# LeafSch.net
KiCad netlist of a schematic drawn in Altium Designer
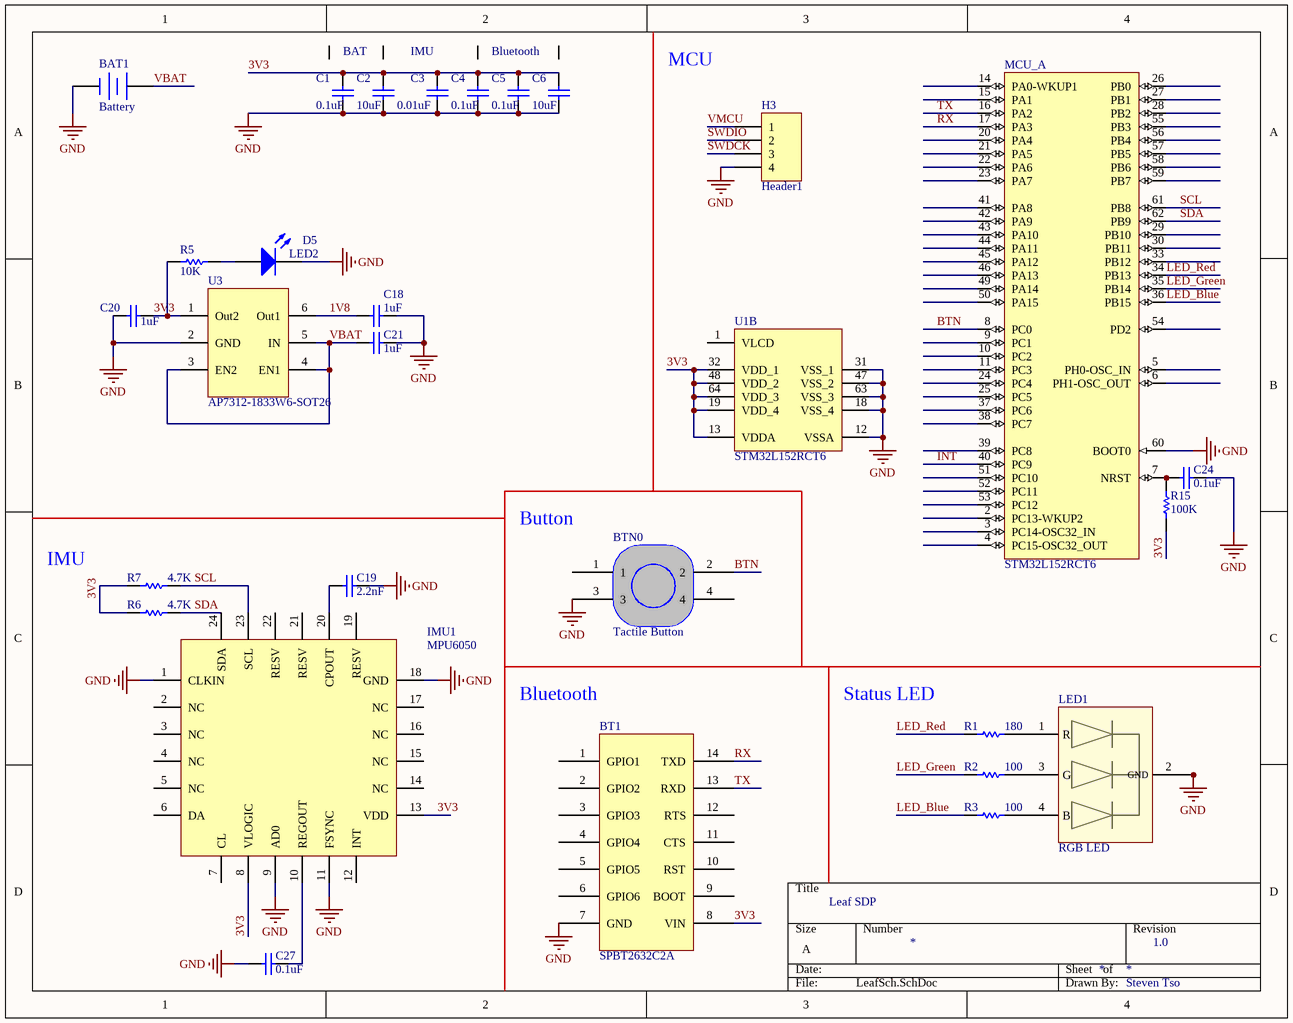
[diagram p0: LeafSch.SchDoc]

(export (version "E")
  (design (tool "Eeschema 10.0.6"))
  (components
    (comp (ref "BAT1")
      (value "Battery")
      (footprint "BAT-2")
      (description "Multicell Battery")
      (fields (field (name "PUBLISHER") "Altium Limited"))
      (libsource (lib "Miscellaneous Devices") (part "Battery"))
    )
    (comp (ref "BT1")
      (value "SPBT2632C2A")
      (footprint "SPBT2632C2A")
      (libsource (lib "myLib") (part "SPBT2632C2A"))
    )
    (comp (ref "BTN0") (value "Tactile Button") (libsource (lib "myLib") (part "Tactile Button")))
    (comp (ref "C1")
      (value "0.1uF")
      (footprint "CAPC0805(2012)100_N")
      (description "CAP 1uF 16V -20% to +80% 0805 (2012 Metric) Thickness 1mm SMD")
      (fields (field (name "TOLERANCE") "-20% to +80%"))
      (libsource (lib "Altium Content Vault") (part "CMP-1036-04751-1"))
    )
    (comp (ref "C2")
      (value "10uF")
      (footprint "CAPC0805(2012)100_N")
      (description "CAP 1uF 16V -20% to +80% 0805 (2012 Metric) Thickness 1mm SMD")
      (fields (field (name "TOLERANCE") "-20% to +80%"))
      (libsource (lib "Altium Content Vault") (part "CMP-1036-04751-1"))
    )
    (comp (ref "C3")
      (value "0.01uF")
      (footprint "CAPC0805(2012)100_N")
      (description "CAP 1uF 16V -20% to +80% 0805 (2012 Metric) Thickness 1mm SMD")
      (fields (field (name "TOLERANCE") "-20% to +80%"))
      (libsource (lib "Altium Content Vault") (part "CMP-1036-04751-1"))
    )
    (comp (ref "C4")
      (value "0.1uF")
      (footprint "CAPC0805(2012)100_N")
      (description "CAP 1uF 16V -20% to +80% 0805 (2012 Metric) Thickness 1mm SMD")
      (fields (field (name "TOLERANCE") "-20% to +80%"))
      (libsource (lib "Altium Content Vault") (part "CMP-1036-04751-1"))
    )
    (comp (ref "C5")
      (value "0.1uF")
      (footprint "CAPC0805(2012)100_N")
      (description "CAP 1uF 16V -20% to +80% 0805 (2012 Metric) Thickness 1mm SMD")
      (fields (field (name "TOLERANCE") "-20% to +80%"))
      (libsource (lib "Altium Content Vault") (part "CMP-1036-04751-1"))
    )
    (comp (ref "C6")
      (value "10uF")
      (footprint "CAPC0805(2012)100_N")
      (description "CAP 1uF 16V -20% to +80% 0805 (2012 Metric) Thickness 1mm SMD")
      (fields (field (name "TOLERANCE") "-20% to +80%"))
      (libsource (lib "Altium Content Vault") (part "CMP-1036-04751-1"))
    )
    (comp (ref "C18")
      (value "1uF")
      (footprint "CAPC0603(1608)100_M")
      (description "CAP 1uF 16V -20% to +80% 0603 (1608 Metric) Thickness 1mm SMD")
      (fields (field (name "TOLERANCE") "-20% to +80%"))
      (libsource (lib "Altium Content Vault") (part "CMP-1035-02739-1"))
    )
    (comp (ref "C19")
      (value "2.2nF")
      (footprint "CAPC0603(1608)100_M")
      (description "CAP 1uF 16V -20% to +80% 0603 (1608 Metric) Thickness 1mm SMD")
      (fields (field (name "TOLERANCE") "-20% to +80%"))
      (libsource (lib "Altium Content Vault") (part "CMP-1035-02739-1"))
    )
    (comp (ref "C20")
      (value "1uF")
      (footprint "CAPC0603(1608)100_M")
      (description "CAP 1uF 16V -20% to +80% 0603 (1608 Metric) Thickness 1mm SMD")
      (fields (field (name "TOLERANCE") "-20% to +80%"))
      (libsource (lib "Altium Content Vault") (part "CMP-1035-02739-1"))
    )
    (comp (ref "C21")
      (value "1uF")
      (footprint "CAPC0603(1608)100_M")
      (description "CAP 1uF 16V -20% to +80% 0603 (1608 Metric) Thickness 1mm SMD")
      (fields (field (name "TOLERANCE") "-20% to +80%"))
      (libsource (lib "Altium Content Vault") (part "CMP-1035-02739-1"))
    )
    (comp (ref "C24")
      (value "0.1uF")
      (footprint "CAPC0603(1608)100_M")
      (description "CAP 1uF 16V -20% to +80% 0603 (1608 Metric) Thickness 1mm SMD")
      (fields (field (name "TOLERANCE") "-20% to +80%"))
      (libsource (lib "Altium Content Vault") (part "CMP-1035-02739-1"))
    )
    (comp (ref "C27")
      (value "0.1uF")
      (footprint "CAPC0603(1608)100_M")
      (description "CAP 1uF 16V -20% to +80% 0603 (1608 Metric) Thickness 1mm SMD")
      (fields (field (name "TOLERANCE") "-20% to +80%"))
      (libsource (lib "Altium Content Vault") (part "CMP-1035-02739-1"))
    )
    (comp (ref "D5")
      (value "LED2")
      (footprint "3.2X1.6X1.1")
      (description "Typical RED, GREEN, YELLOW, AMBER GaAs LED")
      (fields (field (name "PUBLISHER") "Altium Limited"))
      (libsource (lib "Miscellaneous Devices") (part "LED2"))
    )
    (comp (ref "H3")
      (value "Header1")
      (footprint "HDR1X4")
      (description "Header, 4-Pin")
      (fields (field (name "PUBLISHER") "Altium Limited"))
      (libsource (lib "Miscellaneous Connectors") (part "Header 4"))
    )
    (comp (ref "IMU1") (value "MPU6050") (libsource (lib "myLib") (part "MPU6050")))
    (comp (ref "LED1") (value "RGB LED") (libsource (lib "myLib") (part "RGB LED")))
    (comp (ref "MCU_")
      (value "STM32L152RCT6")
      (footprint "STM-LQFP64_N")
      (libsource (lib "STMicroelectronics STM32 L1") (part "STM32L152RCT6"))
    )
    (comp (ref "R1")
      (value "180")
      (footprint "RESC0603(1608)_L")
      (description "10K 0.1W 5% 0603 (1608 Metric)  SMD")
      (fields (field (name "TOLERANCE") "5 %") (field (name "POWER") "0.1 W"))
      (libsource (lib "Altium Content Vault") (part "CMP-1012-00074-1"))
    )
    (comp (ref "R2")
      (value "100")
      (footprint "RESC0603(1608)_L")
      (description "10K 0.1W 5% 0603 (1608 Metric)  SMD")
      (fields (field (name "TOLERANCE") "5 %") (field (name "POWER") "0.1 W"))
      (libsource (lib "Altium Content Vault") (part "CMP-1012-00074-1"))
    )
    (comp (ref "R3")
      (value "100")
      (footprint "RESC0603(1608)_L")
      (description "10K 0.1W 5% 0603 (1608 Metric)  SMD")
      (fields (field (name "TOLERANCE") "5 %") (field (name "POWER") "0.1 W"))
      (libsource (lib "Altium Content Vault") (part "CMP-1012-00074-1"))
    )
    (comp (ref "R5")
      (value "10K")
      (footprint "RESC0603(1608)_L")
      (description "10K 0.1W 5% 0603 (1608 Metric)  SMD")
      (fields (field (name "TOLERANCE") "5 %") (field (name "POWER") "0.1 W"))
      (libsource (lib "Altium Content Vault") (part "CMP-1012-00074-1"))
    )
    (comp (ref "R6")
      (value "4.7K")
      (footprint "RESC0603(1608)_L")
      (description "10K 0.1W 5% 0603 (1608 Metric)  SMD")
      (fields (field (name "TOLERANCE") "5 %") (field (name "POWER") "0.1 W"))
      (libsource (lib "Altium Content Vault") (part "CMP-1012-00074-1"))
    )
    (comp (ref "R7")
      (value "4.7K")
      (footprint "RESC0603(1608)_L")
      (description "10K 0.1W 5% 0603 (1608 Metric)  SMD")
      (fields (field (name "TOLERANCE") "5 %") (field (name "POWER") "0.1 W"))
      (libsource (lib "Altium Content Vault") (part "CMP-1012-00074-1"))
    )
    (comp (ref "R15")
      (value "100K")
      (footprint "RESC0603(1608)_L")
      (description "10K 0.1W 5% 0603 (1608 Metric)  SMD")
      (fields (field (name "TOLERANCE") "5 %") (field (name "POWER") "0.1 W"))
      (libsource (lib "Altium Content Vault") (part "CMP-1012-00074-1"))
    )
    (comp (ref "U1")
      (value "STM32L152RCT6")
      (footprint "STM-LQFP64_N")
      (libsource (lib "STMicroelectronics STM32 L1") (part "STM32L152RCT6"))
    )
    (comp (ref "U3")
      (value "AP7312-1833W6-SOT26")
      (footprint "SOT26A-6AN")
      (libsource (lib "myLib") (part "AP7312-1833W6-SOT26"))
    )
  )
  (nets
    (net (code "1") (name "/1V8") (class "Default")
      (node (ref "C18") (pin "2") (pinfunction "2_2") (pintype "passive"))
      (node (ref "U3") (pin "6") (pinfunction "Out1_6") (pintype "passive"))
    )
    (net (code "2") (name "/3V3") (class "Default")
      (node (ref "BT1") (pin "8") (pinfunction "VIN_8") (pintype "passive"))
      (node (ref "C1") (pin "1") (pinfunction "1_1") (pintype "passive"))
      (node (ref "C2") (pin "1") (pinfunction "1_1") (pintype "passive"))
      (node (ref "C20") (pin "1") (pinfunction "1_1") (pintype "passive"))
      (node (ref "C3") (pin "1") (pinfunction "1_1") (pintype "passive"))
      (node (ref "C4") (pin "1") (pinfunction "1_1") (pintype "passive"))
      (node (ref "C5") (pin "1") (pinfunction "1_1") (pintype "passive"))
      (node (ref "C6") (pin "1") (pinfunction "1_1") (pintype "passive"))
      (node (ref "IMU1") (pin "13") (pinfunction "VDD_13") (pintype "passive"))
      (node (ref "IMU1") (pin "8") (pinfunction "VLOGIC_8") (pintype "passive"))
      (node (ref "R15") (pin "1") (pinfunction "1_1") (pintype "passive"))
      (node (ref "R5") (pin "2") (pinfunction "2_2") (pintype "passive"))
      (node (ref "R6") (pin "1") (pinfunction "1_1") (pintype "passive"))
      (node (ref "R7") (pin "1") (pinfunction "1_1") (pintype "passive"))
      (node (ref "U1") (pin "13") (pinfunction "VDDA_13") (pintype "power_in"))
      (node (ref "U1") (pin "19") (pinfunction "VDD_4_19") (pintype "power_in"))
      (node (ref "U1") (pin "32") (pinfunction "VDD_1_32") (pintype "power_in"))
      (node (ref "U1") (pin "48") (pinfunction "VDD_2_48") (pintype "power_in"))
      (node (ref "U1") (pin "64") (pinfunction "VDD_3_64") (pintype "power_in"))
      (node (ref "U3") (pin "1") (pinfunction "Out2_1") (pintype "passive"))
    )
    (net (code "3") (name "/BTN") (class "Default")
      (node (ref "BTN0") (pin "2") (pinfunction "2_2") (pintype "passive"))
      (node (ref "MCU_") (pin "8") (pinfunction "PC0_8") (pintype "bidirectional"))
    )
    (net (code "4") (name "/INT") (class "Default")
      (node (ref "MCU_") (pin "40") (pinfunction "PC9_40") (pintype "bidirectional"))
    )
    (net (code "5") (name "/LED_Blue") (class "Default")
      (node (ref "MCU_") (pin "36") (pinfunction "PB15_36") (pintype "bidirectional"))
      (node (ref "R3") (pin "2") (pinfunction "2_2") (pintype "passive"))
    )
    (net (code "6") (name "/LED_Green") (class "Default")
      (node (ref "MCU_") (pin "35") (pinfunction "PB14_35") (pintype "bidirectional"))
      (node (ref "R2") (pin "2") (pinfunction "2_2") (pintype "passive"))
    )
    (net (code "7") (name "/LED_Red") (class "Default")
      (node (ref "MCU_") (pin "34") (pinfunction "PB13_34") (pintype "bidirectional"))
      (node (ref "R1") (pin "2") (pinfunction "2_2") (pintype "passive"))
    )
    (net (code "8") (name "/RX") (class "Default")
      (node (ref "BT1") (pin "14") (pinfunction "TXD_14") (pintype "passive"))
      (node (ref "MCU_") (pin "17") (pinfunction "PA3_17") (pintype "bidirectional"))
    )
    (net (code "9") (name "/SCL") (class "Default")
      (node (ref "IMU1") (pin "23") (pinfunction "SCL_23") (pintype "passive"))
      (node (ref "MCU_") (pin "61") (pinfunction "PB8_61") (pintype "bidirectional"))
      (node (ref "R7") (pin "2") (pinfunction "2_2") (pintype "passive"))
    )
    (net (code "10") (name "/SDA") (class "Default")
      (node (ref "IMU1") (pin "24") (pinfunction "SDA_24") (pintype "passive"))
      (node (ref "MCU_") (pin "62") (pinfunction "PB9_62") (pintype "bidirectional"))
      (node (ref "R6") (pin "2") (pinfunction "2_2") (pintype "passive"))
    )
    (net (code "11") (name "/SWDCK") (class "Default")
      (node (ref "H3") (pin "3") (pinfunction "3_3") (pintype "passive"))
    )
    (net (code "12") (name "/SWDIO") (class "Default")
      (node (ref "H3") (pin "2") (pinfunction "2_2") (pintype "passive"))
    )
    (net (code "13") (name "/TX") (class "Default")
      (node (ref "BT1") (pin "13") (pinfunction "RXD_13") (pintype "passive"))
      (node (ref "MCU_") (pin "16") (pinfunction "PA2_16") (pintype "bidirectional"))
    )
    (net (code "14") (name "/VBAT") (class "Default")
      (node (ref "BAT1") (pin "1") (pinfunction "+_1") (pintype "passive"))
      (node (ref "C21") (pin "2") (pinfunction "2_2") (pintype "passive"))
      (node (ref "U3") (pin "3") (pinfunction "EN2_3") (pintype "passive"))
      (node (ref "U3") (pin "4") (pinfunction "EN1_4") (pintype "passive"))
      (node (ref "U3") (pin "5") (pinfunction "IN_5") (pintype "passive"))
    )
    (net (code "15") (name "/VMCU") (class "Default")
      (node (ref "H3") (pin "1") (pinfunction "1_1") (pintype "passive"))
    )
    (net (code "16") (name "GND") (class "Default")
      (node (ref "BAT1") (pin "2") (pinfunction "-_2") (pintype "passive"))
      (node (ref "BT1") (pin "7") (pinfunction "GND_7") (pintype "passive"))
      (node (ref "BTN0") (pin "3") (pinfunction "3_3") (pintype "passive"))
      (node (ref "C1") (pin "2") (pinfunction "2_2") (pintype "passive"))
      (node (ref "C18") (pin "1") (pinfunction "1_1") (pintype "passive"))
      (node (ref "C19") (pin "1") (pinfunction "1_1") (pintype "passive"))
      (node (ref "C2") (pin "2") (pinfunction "2_2") (pintype "passive"))
      (node (ref "C20") (pin "2") (pinfunction "2_2") (pintype "passive"))
      (node (ref "C21") (pin "1") (pinfunction "1_1") (pintype "passive"))
      (node (ref "C24") (pin "1") (pinfunction "1_1") (pintype "passive"))
      (node (ref "C27") (pin "2") (pinfunction "2_2") (pintype "passive"))
      (node (ref "C3") (pin "2") (pinfunction "2_2") (pintype "passive"))
      (node (ref "C4") (pin "2") (pinfunction "2_2") (pintype "passive"))
      (node (ref "C5") (pin "2") (pinfunction "2_2") (pintype "passive"))
      (node (ref "C6") (pin "2") (pinfunction "2_2") (pintype "passive"))
      (node (ref "D5") (pin "2") (pinfunction "K_2") (pintype "passive"))
      (node (ref "H3") (pin "4") (pinfunction "4_4") (pintype "passive"))
      (node (ref "IMU1") (pin "1") (pinfunction "CLKIN_1") (pintype "passive"))
      (node (ref "IMU1") (pin "11") (pinfunction "FSYNC_11") (pintype "passive"))
      (node (ref "IMU1") (pin "18") (pinfunction "GND_18") (pintype "passive"))
      (node (ref "IMU1") (pin "9") (pinfunction "AD0_9") (pintype "passive"))
      (node (ref "LED1") (pin "2") (pinfunction "GND_2") (pintype "passive"))
      (node (ref "MCU_") (pin "60") (pinfunction "BOOT0_60") (pintype "input"))
      (node (ref "U1") (pin "12") (pinfunction "VSSA_12") (pintype "power_in"))
      (node (ref "U1") (pin "18") (pinfunction "VSS_4_18") (pintype "power_in"))
      (node (ref "U1") (pin "31") (pinfunction "VSS_1_31") (pintype "power_in"))
      (node (ref "U1") (pin "47") (pinfunction "VSS_2_47") (pintype "power_in"))
      (node (ref "U1") (pin "63") (pinfunction "VSS_3_63") (pintype "power_in"))
      (node (ref "U3") (pin "2") (pinfunction "GND_2") (pintype "passive"))
    )
    (net (code "17") (name "Net-(D5-A)") (class "Default")
      (node (ref "D5") (pin "1") (pinfunction "A_1") (pintype "passive"))
      (node (ref "R5") (pin "1") (pinfunction "1_1") (pintype "passive"))
    )
    (net (code "18") (name "Net-(IMU1-CPOUT)") (class "Default")
      (node (ref "C19") (pin "2") (pinfunction "2_2") (pintype "passive"))
      (node (ref "IMU1") (pin "20") (pinfunction "CPOUT_20") (pintype "passive"))
    )
    (net (code "19") (name "Net-(IMU1-REGOUT)") (class "Default")
      (node (ref "C27") (pin "1") (pinfunction "1_1") (pintype "passive"))
      (node (ref "IMU1") (pin "10") (pinfunction "REGOUT_10") (pintype "passive"))
    )
    (net (code "20") (name "Net-(LED1-B)") (class "Default")
      (node (ref "LED1") (pin "4") (pinfunction "B_4") (pintype "passive"))
      (node (ref "R3") (pin "1") (pinfunction "1_1") (pintype "passive"))
    )
    (net (code "21") (name "Net-(LED1-G)") (class "Default")
      (node (ref "LED1") (pin "3") (pinfunction "G_3") (pintype "passive"))
      (node (ref "R2") (pin "1") (pinfunction "1_1") (pintype "passive"))
    )
    (net (code "22") (name "Net-(LED1-R)") (class "Default")
      (node (ref "LED1") (pin "1") (pinfunction "R_1") (pintype "passive"))
      (node (ref "R1") (pin "1") (pinfunction "1_1") (pintype "passive"))
    )
    (net (code "23") (name "Net-(MCU_A-NRST)") (class "Default")
      (node (ref "C24") (pin "2") (pinfunction "2_2") (pintype "passive"))
      (node (ref "MCU_") (pin "7") (pinfunction "NRST_7") (pintype "bidirectional"))
      (node (ref "R15") (pin "2") (pinfunction "2_2") (pintype "passive"))
    )
    (net (code "24") (name "unconnected-(BT1-BOOT-Pad9)") (class "Default")
      (node (ref "BT1") (pin "9") (pinfunction "BOOT_9") (pintype "passive"))
    )
    (net (code "25") (name "unconnected-(BT1-CTS-Pad11)") (class "Default")
      (node (ref "BT1") (pin "11") (pinfunction "CTS_11") (pintype "passive"))
    )
    (net (code "26") (name "unconnected-(BT1-GPIO1-Pad1)") (class "Default")
      (node (ref "BT1") (pin "1") (pinfunction "GPIO1_1") (pintype "passive"))
    )
    (net (code "27") (name "unconnected-(BT1-GPIO2-Pad2)") (class "Default")
      (node (ref "BT1") (pin "2") (pinfunction "GPIO2_2") (pintype "passive"))
    )
    (net (code "28") (name "unconnected-(BT1-GPIO3-Pad3)") (class "Default")
      (node (ref "BT1") (pin "3") (pinfunction "GPIO3_3") (pintype "passive"))
    )
    (net (code "29") (name "unconnected-(BT1-GPIO4-Pad4)") (class "Default")
      (node (ref "BT1") (pin "4") (pinfunction "GPIO4_4") (pintype "passive"))
    )
    (net (code "30") (name "unconnected-(BT1-GPIO5-Pad5)") (class "Default")
      (node (ref "BT1") (pin "5") (pinfunction "GPIO5_5") (pintype "passive"))
    )
    (net (code "31") (name "unconnected-(BT1-GPIO6-Pad6)") (class "Default")
      (node (ref "BT1") (pin "6") (pinfunction "GPIO6_6") (pintype "passive"))
    )
    (net (code "32") (name "unconnected-(BT1-RST-Pad10)") (class "Default")
      (node (ref "BT1") (pin "10") (pinfunction "RST_10") (pintype "passive"))
    )
    (net (code "33") (name "unconnected-(BT1-RTS-Pad12)") (class "Default")
      (node (ref "BT1") (pin "12") (pinfunction "RTS_12") (pintype "passive"))
    )
    (net (code "34") (name "unconnected-(BTN0-Pad1)") (class "Default")
      (node (ref "BTN0") (pin "1") (pinfunction "1_1") (pintype "passive"))
    )
    (net (code "35") (name "unconnected-(BTN0-Pad4)") (class "Default")
      (node (ref "BTN0") (pin "4") (pinfunction "4_4") (pintype "passive"))
    )
    (net (code "36") (name "unconnected-(IMU1-CL-Pad7)") (class "Default")
      (node (ref "IMU1") (pin "7") (pinfunction "CL_7") (pintype "passive"))
    )
    (net (code "37") (name "unconnected-(IMU1-DA-Pad6)") (class "Default")
      (node (ref "IMU1") (pin "6") (pinfunction "DA_6") (pintype "passive"))
    )
    (net (code "38") (name "unconnected-(IMU1-INT-Pad12)") (class "Default")
      (node (ref "IMU1") (pin "12") (pinfunction "INT_12") (pintype "passive"))
    )
    (net (code "39") (name "unconnected-(IMU1-NC-Pad2)") (class "Default")
      (node (ref "IMU1") (pin "2") (pinfunction "NC_2") (pintype "passive"))
    )
    (net (code "40") (name "unconnected-(IMU1-NC-Pad3)") (class "Default")
      (node (ref "IMU1") (pin "3") (pinfunction "NC_3") (pintype "passive"))
    )
    (net (code "41") (name "unconnected-(IMU1-NC-Pad4)") (class "Default")
      (node (ref "IMU1") (pin "4") (pinfunction "NC_4") (pintype "passive"))
    )
    (net (code "42") (name "unconnected-(IMU1-NC-Pad5)") (class "Default")
      (node (ref "IMU1") (pin "5") (pinfunction "NC_5") (pintype "passive"))
    )
    (net (code "43") (name "unconnected-(IMU1-NC-Pad14)") (class "Default")
      (node (ref "IMU1") (pin "14") (pinfunction "NC_14") (pintype "passive"))
    )
    (net (code "44") (name "unconnected-(IMU1-NC-Pad15)") (class "Default")
      (node (ref "IMU1") (pin "15") (pinfunction "NC_15") (pintype "passive"))
    )
    (net (code "45") (name "unconnected-(IMU1-NC-Pad16)") (class "Default")
      (node (ref "IMU1") (pin "16") (pinfunction "NC_16") (pintype "passive"))
    )
    (net (code "46") (name "unconnected-(IMU1-NC-Pad17)") (class "Default")
      (node (ref "IMU1") (pin "17") (pinfunction "NC_17") (pintype "passive"))
    )
    (net (code "47") (name "unconnected-(IMU1-RESV-Pad19)") (class "Default")
      (node (ref "IMU1") (pin "19") (pinfunction "RESV_19") (pintype "passive"))
    )
    (net (code "48") (name "unconnected-(IMU1-RESV-Pad21)") (class "Default")
      (node (ref "IMU1") (pin "21") (pinfunction "RESV_21") (pintype "passive"))
    )
    (net (code "49") (name "unconnected-(IMU1-RESV-Pad22)") (class "Default")
      (node (ref "IMU1") (pin "22") (pinfunction "RESV_22") (pintype "passive"))
    )
    (net (code "50") (name "unconnected-(MCU_A-PA0-WKUP1-Pad14)") (class "Default")
      (node (ref "MCU_") (pin "14") (pinfunction "PA0-WKUP1_14") (pintype "bidirectional"))
    )
    (net (code "51") (name "unconnected-(MCU_A-PA1-Pad15)") (class "Default")
      (node (ref "MCU_") (pin "15") (pinfunction "PA1_15") (pintype "bidirectional"))
    )
    (net (code "52") (name "unconnected-(MCU_A-PA4-Pad20)") (class "Default")
      (node (ref "MCU_") (pin "20") (pinfunction "PA4_20") (pintype "bidirectional"))
    )
    (net (code "53") (name "unconnected-(MCU_A-PA5-Pad21)") (class "Default")
      (node (ref "MCU_") (pin "21") (pinfunction "PA5_21") (pintype "bidirectional"))
    )
    (net (code "54") (name "unconnected-(MCU_A-PA6-Pad22)") (class "Default")
      (node (ref "MCU_") (pin "22") (pinfunction "PA6_22") (pintype "bidirectional"))
    )
    (net (code "55") (name "unconnected-(MCU_A-PA7-Pad23)") (class "Default")
      (node (ref "MCU_") (pin "23") (pinfunction "PA7_23") (pintype "bidirectional"))
    )
    (net (code "56") (name "unconnected-(MCU_A-PA8-Pad41)") (class "Default")
      (node (ref "MCU_") (pin "41") (pinfunction "PA8_41") (pintype "bidirectional"))
    )
    (net (code "57") (name "unconnected-(MCU_A-PA9-Pad42)") (class "Default")
      (node (ref "MCU_") (pin "42") (pinfunction "PA9_42") (pintype "bidirectional"))
    )
    (net (code "58") (name "unconnected-(MCU_A-PA10-Pad43)") (class "Default")
      (node (ref "MCU_") (pin "43") (pinfunction "PA10_43") (pintype "bidirectional"))
    )
    (net (code "59") (name "unconnected-(MCU_A-PA11-Pad44)") (class "Default")
      (node (ref "MCU_") (pin "44") (pinfunction "PA11_44") (pintype "bidirectional"))
    )
    (net (code "60") (name "unconnected-(MCU_A-PA12-Pad45)") (class "Default")
      (node (ref "MCU_") (pin "45") (pinfunction "PA12_45") (pintype "bidirectional"))
    )
    (net (code "61") (name "unconnected-(MCU_A-PA13-Pad46)") (class "Default")
      (node (ref "MCU_") (pin "46") (pinfunction "PA13_46") (pintype "bidirectional"))
    )
    (net (code "62") (name "unconnected-(MCU_A-PA14-Pad49)") (class "Default")
      (node (ref "MCU_") (pin "49") (pinfunction "PA14_49") (pintype "bidirectional"))
    )
    (net (code "63") (name "unconnected-(MCU_A-PA15-Pad50)") (class "Default")
      (node (ref "MCU_") (pin "50") (pinfunction "PA15_50") (pintype "bidirectional"))
    )
    (net (code "64") (name "unconnected-(MCU_A-PB0-Pad26)") (class "Default")
      (node (ref "MCU_") (pin "26") (pinfunction "PB0_26") (pintype "bidirectional"))
    )
    (net (code "65") (name "unconnected-(MCU_A-PB1-Pad27)") (class "Default")
      (node (ref "MCU_") (pin "27") (pinfunction "PB1_27") (pintype "bidirectional"))
    )
    (net (code "66") (name "unconnected-(MCU_A-PB2-Pad28)") (class "Default")
      (node (ref "MCU_") (pin "28") (pinfunction "PB2_28") (pintype "bidirectional"))
    )
    (net (code "67") (name "unconnected-(MCU_A-PB3-Pad55)") (class "Default")
      (node (ref "MCU_") (pin "55") (pinfunction "PB3_55") (pintype "bidirectional"))
    )
    (net (code "68") (name "unconnected-(MCU_A-PB4-Pad56)") (class "Default")
      (node (ref "MCU_") (pin "56") (pinfunction "PB4_56") (pintype "bidirectional"))
    )
    (net (code "69") (name "unconnected-(MCU_A-PB5-Pad57)") (class "Default")
      (node (ref "MCU_") (pin "57") (pinfunction "PB5_57") (pintype "bidirectional"))
    )
    (net (code "70") (name "unconnected-(MCU_A-PB6-Pad58)") (class "Default")
      (node (ref "MCU_") (pin "58") (pinfunction "PB6_58") (pintype "bidirectional"))
    )
    (net (code "71") (name "unconnected-(MCU_A-PB7-Pad59)") (class "Default")
      (node (ref "MCU_") (pin "59") (pinfunction "PB7_59") (pintype "bidirectional"))
    )
    (net (code "72") (name "unconnected-(MCU_A-PB10-Pad29)") (class "Default")
      (node (ref "MCU_") (pin "29") (pinfunction "PB10_29") (pintype "bidirectional"))
    )
    (net (code "73") (name "unconnected-(MCU_A-PB11-Pad30)") (class "Default")
      (node (ref "MCU_") (pin "30") (pinfunction "PB11_30") (pintype "bidirectional"))
    )
    (net (code "74") (name "unconnected-(MCU_A-PB12-Pad33)") (class "Default")
      (node (ref "MCU_") (pin "33") (pinfunction "PB12_33") (pintype "bidirectional"))
    )
    (net (code "75") (name "unconnected-(MCU_A-PC1-Pad9)") (class "Default")
      (node (ref "MCU_") (pin "9") (pinfunction "PC1_9") (pintype "bidirectional"))
    )
    (net (code "76") (name "unconnected-(MCU_A-PC2-Pad10)") (class "Default")
      (node (ref "MCU_") (pin "10") (pinfunction "PC2_10") (pintype "bidirectional"))
    )
    (net (code "77") (name "unconnected-(MCU_A-PC3-Pad11)") (class "Default")
      (node (ref "MCU_") (pin "11") (pinfunction "PC3_11") (pintype "bidirectional"))
    )
    (net (code "78") (name "unconnected-(MCU_A-PC4-Pad24)") (class "Default")
      (node (ref "MCU_") (pin "24") (pinfunction "PC4_24") (pintype "bidirectional"))
    )
    (net (code "79") (name "unconnected-(MCU_A-PC5-Pad25)") (class "Default")
      (node (ref "MCU_") (pin "25") (pinfunction "PC5_25") (pintype "bidirectional"))
    )
    (net (code "80") (name "unconnected-(MCU_A-PC6-Pad37)") (class "Default")
      (node (ref "MCU_") (pin "37") (pinfunction "PC6_37") (pintype "bidirectional"))
    )
    (net (code "81") (name "unconnected-(MCU_A-PC7-Pad38)") (class "Default")
      (node (ref "MCU_") (pin "38") (pinfunction "PC7_38") (pintype "bidirectional"))
    )
    (net (code "82") (name "unconnected-(MCU_A-PC8-Pad39)") (class "Default")
      (node (ref "MCU_") (pin "39") (pinfunction "PC8_39") (pintype "bidirectional"))
    )
    (net (code "83") (name "unconnected-(MCU_A-PC10-Pad51)") (class "Default")
      (node (ref "MCU_") (pin "51") (pinfunction "PC10_51") (pintype "bidirectional"))
    )
    (net (code "84") (name "unconnected-(MCU_A-PC11-Pad52)") (class "Default")
      (node (ref "MCU_") (pin "52") (pinfunction "PC11_52") (pintype "bidirectional"))
    )
    (net (code "85") (name "unconnected-(MCU_A-PC12-Pad53)") (class "Default")
      (node (ref "MCU_") (pin "53") (pinfunction "PC12_53") (pintype "bidirectional"))
    )
    (net (code "86") (name "unconnected-(MCU_A-PC13-WKUP2-Pad2)") (class "Default")
      (node (ref "MCU_") (pin "2") (pinfunction "PC13-WKUP2_2") (pintype "bidirectional"))
    )
    (net (code "87") (name "unconnected-(MCU_A-PC14-OSC32_IN-Pad3)") (class "Default")
      (node (ref "MCU_") (pin "3") (pinfunction "PC14-OSC32_IN_3") (pintype "bidirectional"))
    )
    (net (code "88") (name "unconnected-(MCU_A-PC15-OSC32_OUT-Pad4)") (class "Default")
      (node (ref "MCU_") (pin "4") (pinfunction "PC15-OSC32_OUT_4") (pintype "bidirectional"))
    )
    (net (code "89") (name "unconnected-(MCU_A-PD2-Pad54)") (class "Default")
      (node (ref "MCU_") (pin "54") (pinfunction "PD2_54") (pintype "bidirectional"))
    )
    (net (code "90") (name "unconnected-(MCU_A-PH0-OSC_IN-Pad5)") (class "Default")
      (node (ref "MCU_") (pin "5") (pinfunction "PH0-OSC_IN_5") (pintype "bidirectional"))
    )
    (net (code "91") (name "unconnected-(MCU_A-PH1-OSC_OUT-Pad6)") (class "Default")
      (node (ref "MCU_") (pin "6") (pinfunction "PH1-OSC_OUT_6") (pintype "bidirectional"))
    )
    (net (code "92") (name "unconnected-(U1B-VLCD-Pad1)") (class "Default")
      (node (ref "U1") (pin "1") (pinfunction "VLCD_1") (pintype "power_in"))
    )
  )
)
